# alimentation.net
KiCad netlist of a schematic drawn in EAGLE
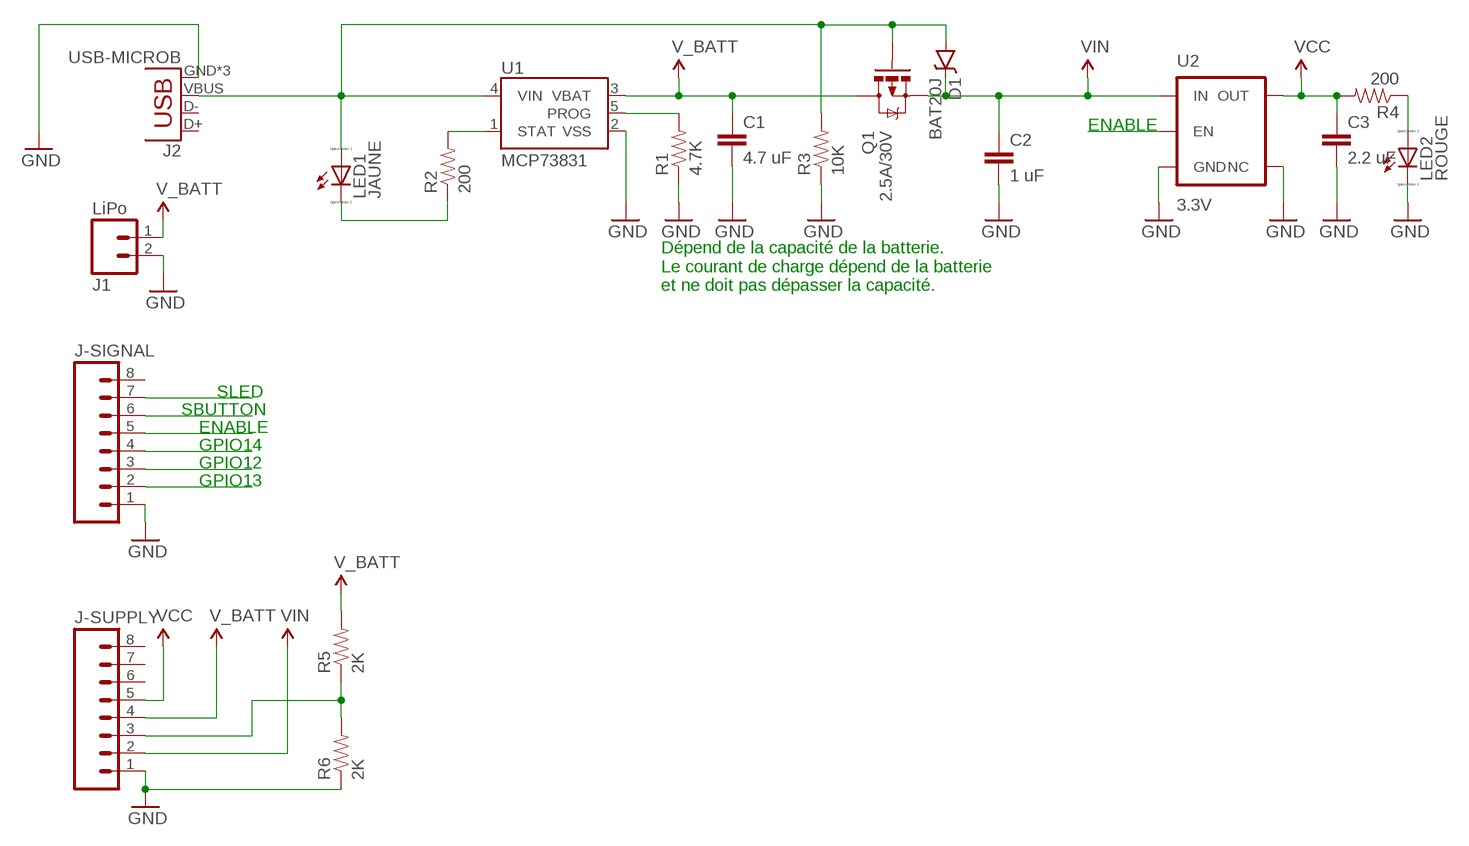
[diagram p0: schematic, sheet 1]

(export (version "E")
  (design (tool "Eeschema 10.0.6"))
  (components
    (comp (ref "C1")
      (value "4.7 uF")
      (footprint "eagle-import:1206")
      (libsource (lib "eagle-import") (part "CAP1206"))
    )
    (comp (ref "C2")
      (value "1 uF")
      (footprint "eagle-import:1206")
      (libsource (lib "eagle-import") (part "CAP1206"))
    )
    (comp (ref "C3")
      (value "2.2 uF")
      (footprint "eagle-import:1206")
      (libsource (lib "eagle-import") (part "CAP1206"))
    )
    (comp (ref "D1")
      (value "BAT20J")
      (footprint "eagle-import:SOD-323")
      (libsource (lib "eagle-import") (part "DIODE-SCHOTTKY-BAT20J"))
    )
    (comp (ref "J-SIGNAL")
      (value "M08")
      (footprint "eagle-import:1X08_ROUND")
      (libsource (lib "eagle-import") (part "M08"))
    )
    (comp (ref "J-SUPPLY")
      (value "M08")
      (footprint "eagle-import:1X08_ROUND")
      (libsource (lib "eagle-import") (part "M08"))
    )
    (comp (ref "J1")
      (value "LiPo")
      (footprint "eagle-import:JST-2-PTH-VERT")
      (libsource (lib "eagle-import") (part "M02JST-PTH-VERT"))
    )
    (comp (ref "J2")
      (value "USB-MICROB")
      (footprint "eagle-import:USB-MICROB")
      (libsource (lib "eagle-import") (part "USB-MICROB"))
    )
    (comp (ref "LED1")
      (value "JAUNE")
      (footprint "eagle-import:LED_1206")
      (libsource (lib "eagle-import") (part "LED_E"))
    )
    (comp (ref "LED2")
      (value "ROUGE")
      (footprint "eagle-import:LED_1206")
      (libsource (lib "eagle-import") (part "LED_E"))
    )
    (comp (ref "Q1")
      (value "2.5A/30V")
      (footprint "eagle-import:SOT23-3")
      (libsource (lib "eagle-import") (part "MOSFET-PCHANNELDMG2307L"))
    )
    (comp (ref "R1")
      (value "4.7K")
      (footprint "eagle-import:0805")
      (libsource (lib "eagle-import") (part "RESISTOR0805-RES"))
    )
    (comp (ref "R2")
      (value "200")
      (footprint "eagle-import:0805")
      (libsource (lib "eagle-import") (part "RESISTOR0805-RES"))
    )
    (comp (ref "R3")
      (value "10K")
      (footprint "eagle-import:0805")
      (libsource (lib "eagle-import") (part "RESISTOR0805-RES"))
    )
    (comp (ref "R4")
      (value "200")
      (footprint "eagle-import:0805")
      (libsource (lib "eagle-import") (part "RESISTOR0805-RES"))
    )
    (comp (ref "R5")
      (value "2K")
      (footprint "eagle-import:0805")
      (libsource (lib "eagle-import") (part "RESISTOR0805-RES"))
    )
    (comp (ref "R6")
      (value "2K")
      (footprint "eagle-import:0805")
      (libsource (lib "eagle-import") (part "RESISTOR0805-RES"))
    )
    (comp (ref "U1")
      (value "MCP73831")
      (footprint "eagle-import:SOT23-5")
      (libsource (lib "eagle-import") (part "MCP73831"))
    )
    (comp (ref "U2")
      (value "3.3V")
      (footprint "eagle-import:SOT23-5")
      (libsource (lib "eagle-import") (part "V_REG_AP2112K-3.3V"))
    )
  )
  (nets
    (net (code "1") (name "/ENABLE") (class "Default")
      (node (ref "J-SIGNAL") (pin "5") (pinfunction "5_5") (pintype "passive"))
      (node (ref "U2") (pin "3") (pinfunction "EN_3") (pintype "input"))
    )
    (net (code "2") (name "GND") (class "Default")
      (node (ref "C1") (pin "2") (pinfunction "2_2") (pintype "passive"))
      (node (ref "C2") (pin "2") (pinfunction "2_2") (pintype "passive"))
      (node (ref "C3") (pin "2") (pinfunction "2_2") (pintype "passive"))
      (node (ref "J-SIGNAL") (pin "1") (pinfunction "1_1") (pintype "passive"))
      (node (ref "J-SUPPLY") (pin "1") (pinfunction "1_1") (pintype "passive"))
      (node (ref "J1") (pin "2") (pinfunction "2_2") (pintype "passive"))
      (node (ref "J2") (pin "GND") (pinfunction "GND_GND") (pintype "bidirectional"))
      (node (ref "J2") (pin "MT1") (pinfunction "GND_MT1") (pintype "bidirectional"))
      (node (ref "J2") (pin "MT2") (pinfunction "GND_MT2") (pintype "bidirectional"))
      (node (ref "LED2") (pin "C") (pinfunction "C_C") (pintype "passive"))
      (node (ref "R1") (pin "1") (pinfunction "1_1") (pintype "passive"))
      (node (ref "R3") (pin "1") (pinfunction "1_1") (pintype "passive"))
      (node (ref "R6") (pin "1") (pinfunction "1_1") (pintype "passive"))
      (node (ref "U1") (pin "2") (pinfunction "VSS_2") (pintype "power_in"))
      (node (ref "U2") (pin "2") (pinfunction "GND_2") (pintype "input"))
      (node (ref "U2") (pin "4") (pinfunction "NC_4") (pintype "input"))
    )
    (net (code "3") (name "Net-(J-SUPPLY-Pad3)") (class "Default")
      (node (ref "J-SUPPLY") (pin "3") (pinfunction "3_3") (pintype "passive"))
      (node (ref "R5") (pin "1") (pinfunction "1_1") (pintype "passive"))
      (node (ref "R6") (pin "2") (pinfunction "2_2") (pintype "passive"))
    )
    (net (code "4") (name "Net-(LED1-PadC)") (class "Default")
      (node (ref "LED1") (pin "C") (pinfunction "C_C") (pintype "passive"))
      (node (ref "R2") (pin "1") (pinfunction "1_1") (pintype "passive"))
    )
    (net (code "5") (name "Net-(LED2-PadA)") (class "Default")
      (node (ref "LED2") (pin "A") (pinfunction "A_A") (pintype "passive"))
      (node (ref "R4") (pin "1") (pinfunction "1_1") (pintype "passive"))
    )
    (net (code "6") (name "Net-(Q1-G)") (class "Default")
      (node (ref "D1") (pin "A") (pinfunction "A_A") (pintype "passive"))
      (node (ref "J2") (pin "VBUS") (pinfunction "VBUS_VBUS") (pintype "bidirectional"))
      (node (ref "LED1") (pin "A") (pinfunction "A_A") (pintype "passive"))
      (node (ref "Q1") (pin "1") (pinfunction "G_1") (pintype "passive"))
      (node (ref "R3") (pin "2") (pinfunction "2_2") (pintype "passive"))
      (node (ref "U1") (pin "4") (pinfunction "VIN_4") (pintype "power_in"))
    )
    (net (code "7") (name "Net-(U1-PROG)") (class "Default")
      (node (ref "R1") (pin "2") (pinfunction "2_2") (pintype "passive"))
      (node (ref "U1") (pin "5") (pinfunction "PROG_5") (pintype "input"))
    )
    (net (code "8") (name "Net-(U1-STAT)") (class "Default")
      (node (ref "R2") (pin "2") (pinfunction "2_2") (pintype "passive"))
      (node (ref "U1") (pin "1") (pinfunction "STAT_1") (pintype "output"))
    )
    (net (code "9") (name "VCC") (class "Default")
      (node (ref "C3") (pin "1") (pinfunction "1_1") (pintype "passive"))
      (node (ref "J-SUPPLY") (pin "5") (pinfunction "5_5") (pintype "passive"))
      (node (ref "R4") (pin "2") (pinfunction "2_2") (pintype "passive"))
      (node (ref "U2") (pin "5") (pinfunction "OUT_5") (pintype "passive"))
    )
    (net (code "10") (name "VIN") (class "Default")
      (node (ref "C2") (pin "1") (pinfunction "1_1") (pintype "passive"))
      (node (ref "D1") (pin "C") (pinfunction "C_C") (pintype "passive"))
      (node (ref "J-SUPPLY") (pin "2") (pinfunction "2_2") (pintype "passive"))
      (node (ref "Q1") (pin "2") (pinfunction "S_2") (pintype "passive"))
      (node (ref "U2") (pin "1") (pinfunction "IN_1") (pintype "input"))
    )
    (net (code "11") (name "V_BATT") (class "Default")
      (node (ref "C1") (pin "1") (pinfunction "1_1") (pintype "passive"))
      (node (ref "J-SUPPLY") (pin "4") (pinfunction "4_4") (pintype "passive"))
      (node (ref "J1") (pin "1") (pinfunction "1_1") (pintype "passive"))
      (node (ref "Q1") (pin "3") (pinfunction "D_3") (pintype "passive"))
      (node (ref "R5") (pin "2") (pinfunction "2_2") (pintype "passive"))
      (node (ref "U1") (pin "3") (pinfunction "VBAT_3") (pintype "power_in"))
    )
    (net (code "12") (name "unconnected-(J-SIGNAL-Pad2)") (class "Default")
      (node (ref "J-SIGNAL") (pin "2") (pinfunction "2_2") (pintype "passive"))
    )
    (net (code "13") (name "unconnected-(J-SIGNAL-Pad3)") (class "Default")
      (node (ref "J-SIGNAL") (pin "3") (pinfunction "3_3") (pintype "passive"))
    )
    (net (code "14") (name "unconnected-(J-SIGNAL-Pad4)") (class "Default")
      (node (ref "J-SIGNAL") (pin "4") (pinfunction "4_4") (pintype "passive"))
    )
    (net (code "15") (name "unconnected-(J-SIGNAL-Pad6)") (class "Default")
      (node (ref "J-SIGNAL") (pin "6") (pinfunction "6_6") (pintype "passive"))
    )
    (net (code "16") (name "unconnected-(J-SIGNAL-Pad7)") (class "Default")
      (node (ref "J-SIGNAL") (pin "7") (pinfunction "7_7") (pintype "passive"))
    )
    (net (code "17") (name "unconnected-(J-SIGNAL-Pad8)") (class "Default")
      (node (ref "J-SIGNAL") (pin "8") (pinfunction "8_8") (pintype "passive"))
    )
    (net (code "18") (name "unconnected-(J-SUPPLY-Pad6)") (class "Default")
      (node (ref "J-SUPPLY") (pin "6") (pinfunction "6_6") (pintype "passive"))
    )
    (net (code "19") (name "unconnected-(J-SUPPLY-Pad7)") (class "Default")
      (node (ref "J-SUPPLY") (pin "7") (pinfunction "7_7") (pintype "passive"))
    )
    (net (code "20") (name "unconnected-(J-SUPPLY-Pad8)") (class "Default")
      (node (ref "J-SUPPLY") (pin "8") (pinfunction "8_8") (pintype "passive"))
    )
    (net (code "21") (name "unconnected-(J2-PadD+)") (class "Default")
      (node (ref "J2") (pin "D+") (pinfunction "D+_D+") (pintype "bidirectional"))
    )
    (net (code "22") (name "unconnected-(J2-PadD-)") (class "Default")
      (node (ref "J2") (pin "D-") (pinfunction "D-_D-") (pintype "bidirectional"))
    )
  )
)
